# nutrino.net
KiCad netlist of a schematic drawn in EAGLE
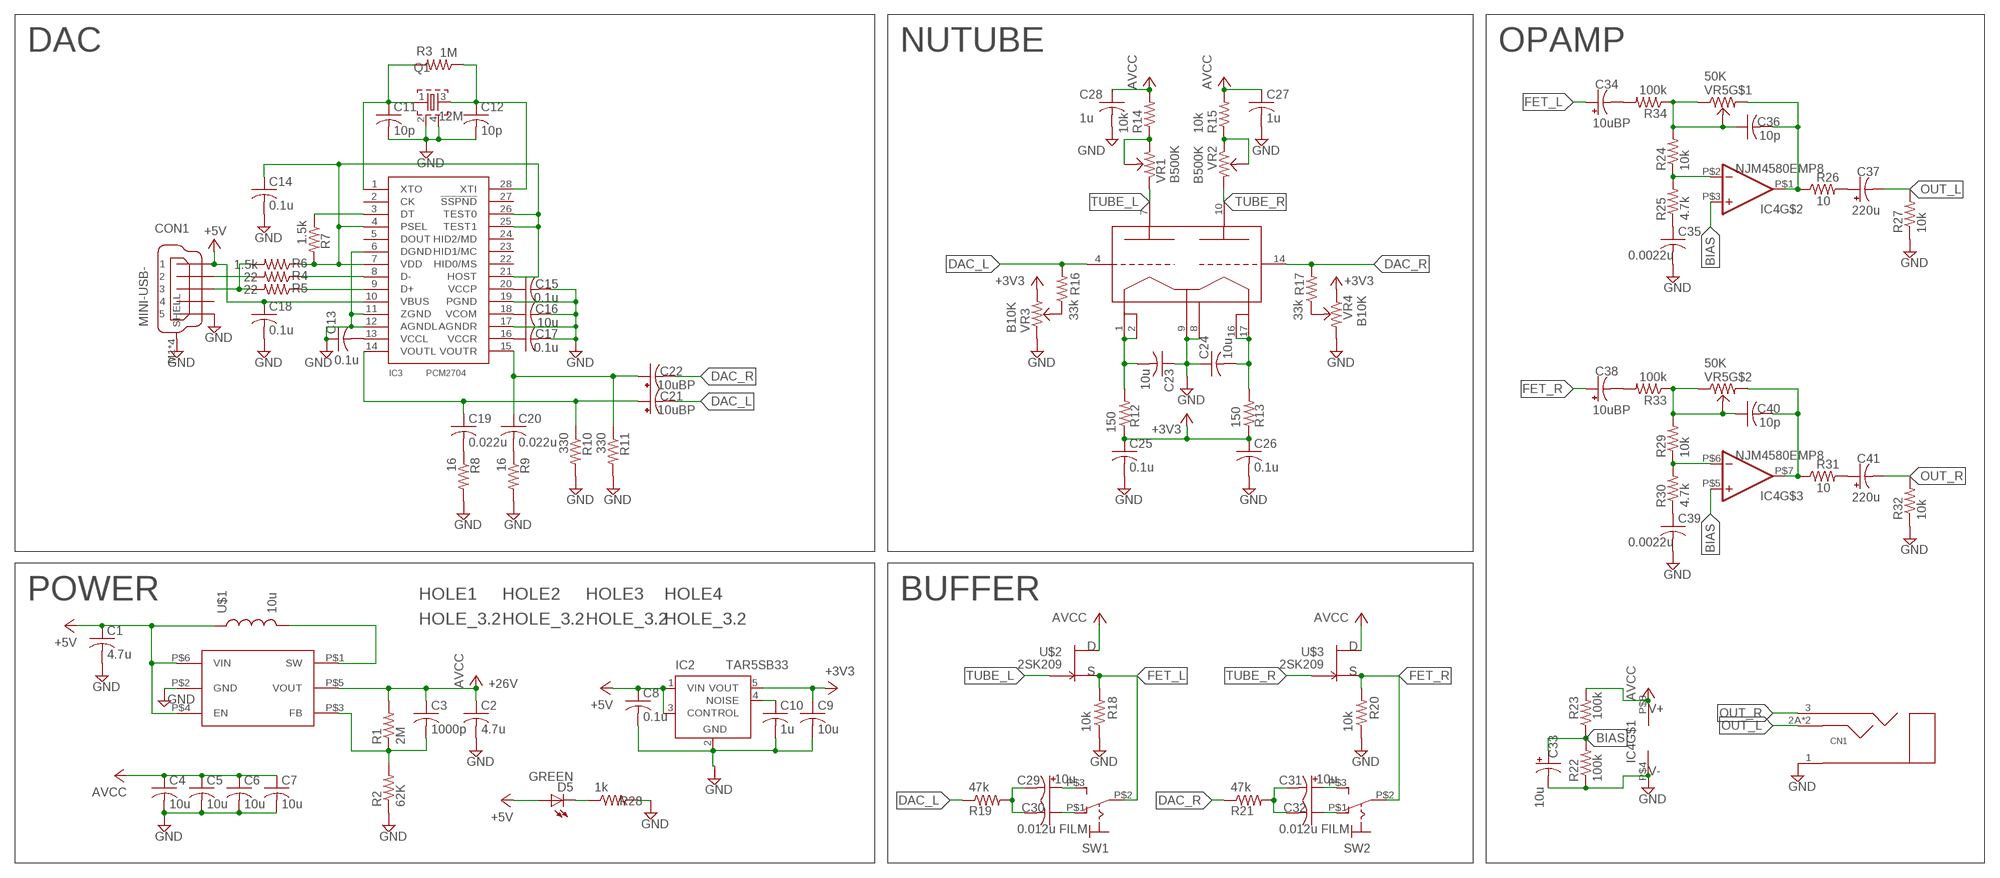
[diagram p0: schematic, sheet 1]

(export (version "E")
  (design (tool "Eeschema 10.0.6"))
  (components
    (comp (ref "C1")
      (value "4.7u")
      (footprint "eagle-import:2012-C")
      (libsource (lib "eagle-import") (part "C-2012"))
    )
    (comp (ref "C2")
      (value "4.7u")
      (footprint "eagle-import:2012-C")
      (libsource (lib "eagle-import") (part "C-2012"))
    )
    (comp (ref "C3")
      (value "1000p")
      (footprint "eagle-import:2012-C")
      (libsource (lib "eagle-import") (part "C-2012"))
    )
    (comp (ref "C4")
      (value "10u")
      (footprint "eagle-import:2012-C")
      (libsource (lib "eagle-import") (part "C-2012"))
    )
    (comp (ref "C5")
      (value "10u")
      (footprint "eagle-import:2012-C")
      (libsource (lib "eagle-import") (part "C-2012"))
    )
    (comp (ref "C6")
      (value "10u")
      (footprint "eagle-import:2012-C")
      (libsource (lib "eagle-import") (part "C-2012"))
    )
    (comp (ref "C7")
      (value "10u")
      (footprint "eagle-import:2012-C")
      (libsource (lib "eagle-import") (part "C-2012"))
    )
    (comp (ref "C8")
      (value "0.1u")
      (footprint "eagle-import:2012-C")
      (libsource (lib "eagle-import") (part "C-2012"))
    )
    (comp (ref "C9")
      (value "10u")
      (footprint "eagle-import:2012-C")
      (libsource (lib "eagle-import") (part "C-2012"))
    )
    (comp (ref "C10")
      (value "1u")
      (footprint "eagle-import:2012-C")
      (libsource (lib "eagle-import") (part "C-2012"))
    )
    (comp (ref "C11")
      (value "10p")
      (footprint "eagle-import:2012-C")
      (libsource (lib "eagle-import") (part "C-2012"))
    )
    (comp (ref "C12")
      (value "10p")
      (footprint "eagle-import:2012-C")
      (libsource (lib "eagle-import") (part "C-2012"))
    )
    (comp (ref "C13")
      (value "0.1u")
      (footprint "eagle-import:2012-C")
      (libsource (lib "eagle-import") (part "C-2012"))
    )
    (comp (ref "C14")
      (value "0.1u")
      (footprint "eagle-import:2012-C")
      (libsource (lib "eagle-import") (part "C-2012"))
    )
    (comp (ref "C15")
      (value "0.1u")
      (footprint "eagle-import:2012-C")
      (libsource (lib "eagle-import") (part "C-2012"))
    )
    (comp (ref "C16")
      (value "10u")
      (footprint "eagle-import:3216")
      (libsource (lib "eagle-import") (part "C-3216"))
    )
    (comp (ref "C17")
      (value "0.1u")
      (footprint "eagle-import:2012-C")
      (libsource (lib "eagle-import") (part "C-2012"))
    )
    (comp (ref "C18")
      (value "0.1u")
      (footprint "eagle-import:2012-C")
      (libsource (lib "eagle-import") (part "C-2012"))
    )
    (comp (ref "C19")
      (value "0.022u")
      (footprint "eagle-import:2012-C")
      (libsource (lib "eagle-import") (part "C-2012"))
    )
    (comp (ref "C20")
      (value "0.022u")
      (footprint "eagle-import:2012-C")
      (libsource (lib "eagle-import") (part "C-2012"))
    )
    (comp (ref "C21")
      (value "10uBP")
      (footprint "eagle-import:E2,5-7")
      (libsource (lib "eagle-import") (part "CC-2.5-7"))
    )
    (comp (ref "C22")
      (value "10uBP")
      (footprint "eagle-import:E2,5-7")
      (libsource (lib "eagle-import") (part "CC-2.5-7"))
    )
    (comp (ref "C23")
      (value "10u")
      (footprint "eagle-import:3216")
      (libsource (lib "eagle-import") (part "C-3216"))
    )
    (comp (ref "C24")
      (value "10u")
      (footprint "eagle-import:3216")
      (libsource (lib "eagle-import") (part "C-3216"))
    )
    (comp (ref "C25")
      (value "0.1u")
      (footprint "eagle-import:2012-C")
      (libsource (lib "eagle-import") (part "C-2012"))
    )
    (comp (ref "C26")
      (value "0.1u")
      (footprint "eagle-import:2012-C")
      (libsource (lib "eagle-import") (part "C-2012"))
    )
    (comp (ref "C27")
      (value "1u")
      (footprint "eagle-import:2012-C")
      (libsource (lib "eagle-import") (part "C-2012"))
    )
    (comp (ref "C28")
      (value "1u")
      (footprint "eagle-import:2012-C")
      (libsource (lib "eagle-import") (part "C-2012"))
    )
    (comp (ref "C29")
      (value "10u")
      (footprint "eagle-import:E2,5-7")
      (libsource (lib "eagle-import") (part "CC-2.5-7"))
    )
    (comp (ref "C30")
      (value "0.012u FILM")
      (footprint "eagle-import:C050-024X044")
      (libsource (lib "eagle-import") (part "C/5"))
    )
    (comp (ref "C31")
      (value "10u")
      (footprint "eagle-import:E2,5-7")
      (libsource (lib "eagle-import") (part "CC-2.5-7"))
    )
    (comp (ref "C32")
      (value "0.012u FILM")
      (footprint "eagle-import:C050-024X044")
      (libsource (lib "eagle-import") (part "C/5"))
    )
    (comp (ref "C33")
      (value "10u")
      (footprint "eagle-import:E2,5-7")
      (libsource (lib "eagle-import") (part "CC-2.5-7"))
    )
    (comp (ref "C34")
      (value "10uBP")
      (footprint "eagle-import:E2,5-7")
      (libsource (lib "eagle-import") (part "CC-2.5-7"))
    )
    (comp (ref "C35")
      (value "0.0022u")
      (footprint "eagle-import:2012-C")
      (libsource (lib "eagle-import") (part "C-2012"))
    )
    (comp (ref "C36")
      (value "10p")
      (footprint "eagle-import:2012-C")
      (libsource (lib "eagle-import") (part "C-2012"))
    )
    (comp (ref "C37")
      (value "220u")
      (footprint "eagle-import:E2,5-7")
      (libsource (lib "eagle-import") (part "CC-2.5-7"))
    )
    (comp (ref "C38")
      (value "10uBP")
      (footprint "eagle-import:E2,5-7")
      (libsource (lib "eagle-import") (part "CC-2.5-7"))
    )
    (comp (ref "C39")
      (value "0.0022u")
      (footprint "eagle-import:2012-C")
      (libsource (lib "eagle-import") (part "C-2012"))
    )
    (comp (ref "C40")
      (value "10p")
      (footprint "eagle-import:2012-C")
      (libsource (lib "eagle-import") (part "C-2012"))
    )
    (comp (ref "C41")
      (value "220u")
      (footprint "eagle-import:E2,5-7")
      (libsource (lib "eagle-import") (part "CC-2.5-7"))
    )
    (comp (ref "CN1")
      (value "STEREO-3.5-MJ8435")
      (footprint "eagle-import:MJ8435")
      (libsource (lib "eagle-import") (part "STEREO-3.5-MJ8435"))
    )
    (comp (ref "CON1")
      (value "MINI-USB-")
      (footprint "eagle-import:UX60A-MB-5ST")
      (libsource (lib "eagle-import") (part "MINI-USB-"))
    )
    (comp (ref "D5")
      (value "GREEN")
      (footprint "eagle-import:D2012")
      (libsource (lib "eagle-import") (part "LED-SMD2012"))
    )
    (comp (ref "HOLE1")
      (value "HOLE_3.2")
      (footprint "eagle-import:HOLE_3.2")
      (libsource (lib "eagle-import") (part "HOLE_3.2"))
    )
    (comp (ref "HOLE2")
      (value "HOLE_3.2")
      (footprint "eagle-import:HOLE_3.2")
      (libsource (lib "eagle-import") (part "HOLE_3.2"))
    )
    (comp (ref "HOLE3")
      (value "HOLE_3.2")
      (footprint "eagle-import:HOLE_3.2")
      (libsource (lib "eagle-import") (part "HOLE_3.2"))
    )
    (comp (ref "HOLE4")
      (value "HOLE_3.2")
      (footprint "eagle-import:HOLE_3.2")
      (libsource (lib "eagle-import") (part "HOLE_3.2"))
    )
    (comp (ref "IC1")
      (value "TLV61046A")
      (footprint "eagle-import:SOT23-6")
      (libsource (lib "eagle-import") (part "TLV61046A"))
    )
    (comp (ref "IC2")
      (value "TAR5SB33")
      (footprint "eagle-import:SSOP5-P-0.95")
      (libsource (lib "eagle-import") (part "TAR5SB33"))
    )
    (comp (ref "IC3")
      (value "PCM2704")
      (footprint "eagle-import:SSOP28")
      (libsource (lib "eagle-import") (part "PCM2704"))
    )
    (comp (ref "IC4")
      (value "NJM4580EMP8")
      (footprint "eagle-import:EMP8")
      (libsource (lib "eagle-import") (part "NJM4580EMP8"))
    )
    (comp (ref "Q1")
      (value "12M")
      (footprint "eagle-import:FA-238V")
      (libsource (lib "eagle-import") (part "FA-238V"))
    )
    (comp (ref "R1")
      (value "2M")
      (footprint "eagle-import:2012-R")
      (libsource (lib "eagle-import") (part "Passive_Robotech_29513872_R-2012"))
    )
    (comp (ref "R2")
      (value "62K")
      (footprint "eagle-import:2012-R")
      (libsource (lib "eagle-import") (part "Passive_Robotech_29513872_R-2012"))
    )
    (comp (ref "R3")
      (value "1M")
      (footprint "eagle-import:2012-R")
      (libsource (lib "eagle-import") (part "Passive_Robotech_29513872_R-2012"))
    )
    (comp (ref "R4")
      (value "22")
      (footprint "eagle-import:2012-R")
      (libsource (lib "eagle-import") (part "Passive_Robotech_29513872_R-2012"))
    )
    (comp (ref "R5")
      (value "22")
      (footprint "eagle-import:2012-R")
      (libsource (lib "eagle-import") (part "Passive_Robotech_29513872_R-2012"))
    )
    (comp (ref "R6")
      (value "1.5k")
      (footprint "eagle-import:2012-R")
      (libsource (lib "eagle-import") (part "Passive_Robotech_29513872_R-2012"))
    )
    (comp (ref "R7")
      (value "1.5k")
      (footprint "eagle-import:2012-R")
      (libsource (lib "eagle-import") (part "Passive_Robotech_29513872_R-2012"))
    )
    (comp (ref "R8")
      (value "16")
      (footprint "eagle-import:2012-R")
      (libsource (lib "eagle-import") (part "Passive_Robotech_29513872_R-2012"))
    )
    (comp (ref "R9")
      (value "16")
      (footprint "eagle-import:2012-R")
      (libsource (lib "eagle-import") (part "Passive_Robotech_29513872_R-2012"))
    )
    (comp (ref "R10")
      (value "330")
      (footprint "eagle-import:2012-R")
      (libsource (lib "eagle-import") (part "Passive_Robotech_29513872_R-2012"))
    )
    (comp (ref "R11")
      (value "330")
      (footprint "eagle-import:2012-R")
      (libsource (lib "eagle-import") (part "Passive_Robotech_29513872_R-2012"))
    )
    (comp (ref "R12")
      (value "150")
      (footprint "eagle-import:2012-R")
      (libsource (lib "eagle-import") (part "R-2012"))
    )
    (comp (ref "R13")
      (value "150")
      (footprint "eagle-import:2012-R")
      (libsource (lib "eagle-import") (part "R-2012"))
    )
    (comp (ref "R14")
      (value "10k")
      (footprint "eagle-import:2012-R")
      (libsource (lib "eagle-import") (part "R-2012"))
    )
    (comp (ref "R15")
      (value "10k")
      (footprint "eagle-import:2012-R")
      (libsource (lib "eagle-import") (part "R-2012"))
    )
    (comp (ref "R16")
      (value "33k")
      (footprint "eagle-import:2012-R")
      (libsource (lib "eagle-import") (part "R-2012"))
    )
    (comp (ref "R17")
      (value "33k")
      (footprint "eagle-import:2012-R")
      (libsource (lib "eagle-import") (part "R-2012"))
    )
    (comp (ref "R18")
      (value "10k")
      (footprint "eagle-import:2012-R")
      (libsource (lib "eagle-import") (part "R-2012"))
    )
    (comp (ref "R19")
      (value "47k")
      (footprint "eagle-import:2012-R")
      (libsource (lib "eagle-import") (part "R-2012"))
    )
    (comp (ref "R20")
      (value "10k")
      (footprint "eagle-import:2012-R")
      (libsource (lib "eagle-import") (part "R-2012"))
    )
    (comp (ref "R21")
      (value "47k")
      (footprint "eagle-import:2012-R")
      (libsource (lib "eagle-import") (part "R-2012"))
    )
    (comp (ref "R22")
      (value "100k")
      (footprint "eagle-import:2012-R")
      (libsource (lib "eagle-import") (part "R-2012"))
    )
    (comp (ref "R23")
      (value "100k")
      (footprint "eagle-import:2012-R")
      (libsource (lib "eagle-import") (part "R-2012"))
    )
    (comp (ref "R24")
      (value "10k")
      (footprint "eagle-import:2012-R")
      (libsource (lib "eagle-import") (part "R-2012"))
    )
    (comp (ref "R25")
      (value "4.7k")
      (footprint "eagle-import:2012-R")
      (libsource (lib "eagle-import") (part "R-2012"))
    )
    (comp (ref "R26")
      (value "10")
      (footprint "eagle-import:4532")
      (libsource (lib "eagle-import") (part "R-4532"))
    )
    (comp (ref "R27")
      (value "10k")
      (footprint "eagle-import:2012-R")
      (libsource (lib "eagle-import") (part "R-2012"))
    )
    (comp (ref "R28")
      (value "1k")
      (footprint "eagle-import:2012-R")
      (libsource (lib "eagle-import") (part "R-2012"))
    )
    (comp (ref "R29")
      (value "10k")
      (footprint "eagle-import:2012-R")
      (libsource (lib "eagle-import") (part "R-2012"))
    )
    (comp (ref "R30")
      (value "4.7k")
      (footprint "eagle-import:2012-R")
      (libsource (lib "eagle-import") (part "R-2012"))
    )
    (comp (ref "R31")
      (value "10")
      (footprint "eagle-import:4532")
      (libsource (lib "eagle-import") (part "R-4532"))
    )
    (comp (ref "R32")
      (value "10k")
      (footprint "eagle-import:2012-R")
      (libsource (lib "eagle-import") (part "R-2012"))
    )
    (comp (ref "R33")
      (value "100k")
      (footprint "eagle-import:2012-R")
      (libsource (lib "eagle-import") (part "R-2012"))
    )
    (comp (ref "R34")
      (value "100k")
      (footprint "eagle-import:2012-R")
      (libsource (lib "eagle-import") (part "R-2012"))
    )
    (comp (ref "SW1")
      (value "SLIDESW_SS12D01G4")
      (footprint "eagle-import:SS12D01G4")
      (libsource (lib "eagle-import") (part "SLIDESW_SS12D01G4"))
    )
    (comp (ref "SW2")
      (value "SLIDESW_SS12D01G4")
      (footprint "eagle-import:SS12D01G4")
      (libsource (lib "eagle-import") (part "SLIDESW_SS12D01G4"))
    )
    (comp (ref "U$1")
      (value "10u")
      (footprint "eagle-import:NR10050T")
      (libsource (lib "eagle-import") (part "INDUCTOR-NR10050T"))
    )
    (comp (ref "U$2")
      (value "2SK209")
      (footprint "eagle-import:SC59")
      (libsource (lib "eagle-import") (part "2SK209"))
    )
    (comp (ref "U$3")
      (value "2SK209")
      (footprint "eagle-import:SC59")
      (libsource (lib "eagle-import") (part "2SK209"))
    )
    (comp (ref "U1")
      (value "NUTUBE_6P1_1")
      (footprint "eagle-import:NUTUBE_6P1_1")
      (libsource (lib "eagle-import") (part "NUTUBE_6P1_1"))
    )
    (comp (ref "VR1")
      (value "B500K")
      (footprint "eagle-import:VR2")
      (libsource (lib "eagle-import") (part "VR2"))
    )
    (comp (ref "VR2")
      (value "B500K")
      (footprint "eagle-import:VR2")
      (libsource (lib "eagle-import") (part "VR2"))
    )
    (comp (ref "VR3")
      (value "B10K")
      (footprint "eagle-import:VR2")
      (libsource (lib "eagle-import") (part "VR2"))
    )
    (comp (ref "VR4")
      (value "B10K")
      (footprint "eagle-import:VR2")
      (libsource (lib "eagle-import") (part "VR2"))
    )
    (comp (ref "VR5")
      (value "50K")
      (footprint "eagle-import:VR2C")
      (libsource (lib "eagle-import") (part "VR2C"))
    )
  )
  (nets
    (net (code "1") (name "+3V3") (class "Default")
      (node (ref "C25") (pin "1") (pinfunction "1_1") (pintype "passive"))
      (node (ref "C26") (pin "1") (pinfunction "1_1") (pintype "passive"))
      (node (ref "C9") (pin "1") (pinfunction "1_1") (pintype "passive"))
      (node (ref "IC2") (pin "5") (pinfunction "VOUT_5") (pintype "power_in"))
      (node (ref "R12") (pin "1") (pinfunction "1_1") (pintype "passive"))
      (node (ref "R13") (pin "1") (pinfunction "1_1") (pintype "passive"))
      (node (ref "VR3") (pin "2") (pinfunction "2_2") (pintype "passive"))
      (node (ref "VR4") (pin "1") (pinfunction "1_1") (pintype "passive"))
    )
    (net (code "2") (name "+5V") (class "Default")
      (node (ref "C1") (pin "1") (pinfunction "1_1") (pintype "passive"))
      (node (ref "C18") (pin "1") (pinfunction "1_1") (pintype "passive"))
      (node (ref "C8") (pin "1") (pinfunction "1_1") (pintype "passive"))
      (node (ref "CON1") (pin "1") (pinfunction "1_1") (pintype "input"))
      (node (ref "D5") (pin "A") (pinfunction "A_A") (pintype "passive"))
      (node (ref "IC1") (pin "P$4") (pinfunction "EN_P$4") (pintype "bidirectional"))
      (node (ref "IC1") (pin "P$6") (pinfunction "VIN_P$6") (pintype "bidirectional"))
      (node (ref "IC2") (pin "1") (pinfunction "VIN_1") (pintype "input"))
      (node (ref "IC2") (pin "3") (pinfunction "CONTROL_3") (pintype "input"))
      (node (ref "IC3") (pin "10") (pinfunction "VBUS_10") (pintype "power_in"))
      (node (ref "U$1") (pin "1") (pinfunction "1_1") (pintype "passive"))
    )
    (net (code "3") (name "AVCC") (class "Default")
      (node (ref "C2") (pin "1") (pinfunction "1_1") (pintype "passive"))
      (node (ref "C27") (pin "1") (pinfunction "1_1") (pintype "passive"))
      (node (ref "C28") (pin "1") (pinfunction "1_1") (pintype "passive"))
      (node (ref "C3") (pin "1") (pinfunction "1_1") (pintype "passive"))
      (node (ref "C4") (pin "1") (pinfunction "1_1") (pintype "passive"))
      (node (ref "C5") (pin "1") (pinfunction "1_1") (pintype "passive"))
      (node (ref "C6") (pin "1") (pinfunction "1_1") (pintype "passive"))
      (node (ref "C7") (pin "1") (pinfunction "1_1") (pintype "passive"))
      (node (ref "IC1") (pin "P$5") (pinfunction "VOUT_P$5") (pintype "bidirectional"))
      (node (ref "IC4") (pin "P$8") (pinfunction "V+_P$8") (pintype "power_in"))
      (node (ref "R1") (pin "2") (pinfunction "2_2") (pintype "passive"))
      (node (ref "R14") (pin "2") (pinfunction "2_2") (pintype "passive"))
      (node (ref "R15") (pin "2") (pinfunction "2_2") (pintype "passive"))
      (node (ref "R23") (pin "2") (pinfunction "2_2") (pintype "passive"))
      (node (ref "U$2") (pin "E") (pinfunction "D_E") (pintype "passive"))
      (node (ref "U$3") (pin "E") (pinfunction "D_E") (pintype "passive"))
    )
    (net (code "4") (name "BIAS") (class "Default")
      (node (ref "C33") (pin "+") (pinfunction "+_+") (pintype "passive"))
      (node (ref "IC4") (pin "P$3") (pinfunction "+IN_P$3") (pintype "input"))
      (node (ref "IC4") (pin "P$5") (pinfunction "+IN_P$5") (pintype "input"))
      (node (ref "R22") (pin "2") (pinfunction "2_2") (pintype "passive"))
      (node (ref "R23") (pin "1") (pinfunction "1_1") (pintype "passive"))
    )
    (net (code "5") (name "DAC_L") (class "Default")
      (node (ref "C21") (pin "-") (pinfunction "-_-") (pintype "passive"))
      (node (ref "R16") (pin "2") (pinfunction "2_2") (pintype "passive"))
      (node (ref "R19") (pin "1") (pinfunction "1_1") (pintype "passive"))
      (node (ref "U1") (pin "4") (pinfunction "G1_4_4") (pintype "passive"))
    )
    (net (code "6") (name "DAC_R") (class "Default")
      (node (ref "C22") (pin "-") (pinfunction "-_-") (pintype "passive"))
      (node (ref "R17") (pin "2") (pinfunction "2_2") (pintype "passive"))
      (node (ref "R21") (pin "1") (pinfunction "1_1") (pintype "passive"))
      (node (ref "U1") (pin "14") (pinfunction "G2_14_14") (pintype "passive"))
    )
    (net (code "7") (name "FET_L") (class "Default")
      (node (ref "C34") (pin "+") (pinfunction "+_+") (pintype "passive"))
      (node (ref "R18") (pin "2") (pinfunction "2_2") (pintype "passive"))
      (node (ref "SW1") (pin "P$2") (pinfunction "P_P$2") (pintype "passive"))
      (node (ref "U$2") (pin "B") (pinfunction "S_B") (pintype "passive"))
    )
    (net (code "8") (name "FET_R") (class "Default")
      (node (ref "C38") (pin "+") (pinfunction "+_+") (pintype "passive"))
      (node (ref "R20") (pin "2") (pinfunction "2_2") (pintype "passive"))
      (node (ref "SW2") (pin "P$2") (pinfunction "P_P$2") (pintype "passive"))
      (node (ref "U$3") (pin "B") (pinfunction "S_B") (pintype "passive"))
    )
    (net (code "9") (name "GND") (class "Default")
      (node (ref "C1") (pin "2") (pinfunction "2_2") (pintype "passive"))
      (node (ref "C10") (pin "2") (pinfunction "2_2") (pintype "passive"))
      (node (ref "C11") (pin "2") (pinfunction "2_2") (pintype "passive"))
      (node (ref "C12") (pin "2") (pinfunction "2_2") (pintype "passive"))
      (node (ref "C13") (pin "1") (pinfunction "1_1") (pintype "passive"))
      (node (ref "C14") (pin "2") (pinfunction "2_2") (pintype "passive"))
      (node (ref "C15") (pin "2") (pinfunction "2_2") (pintype "passive"))
      (node (ref "C16") (pin "2") (pinfunction "2_2") (pintype "passive"))
      (node (ref "C17") (pin "2") (pinfunction "2_2") (pintype "passive"))
      (node (ref "C18") (pin "2") (pinfunction "2_2") (pintype "passive"))
      (node (ref "C2") (pin "2") (pinfunction "2_2") (pintype "passive"))
      (node (ref "C23") (pin "1") (pinfunction "1_1") (pintype "passive"))
      (node (ref "C24") (pin "1") (pinfunction "1_1") (pintype "passive"))
      (node (ref "C25") (pin "2") (pinfunction "2_2") (pintype "passive"))
      (node (ref "C26") (pin "2") (pinfunction "2_2") (pintype "passive"))
      (node (ref "C27") (pin "2") (pinfunction "2_2") (pintype "passive"))
      (node (ref "C28") (pin "2") (pinfunction "2_2") (pintype "passive"))
      (node (ref "C33") (pin "-") (pinfunction "-_-") (pintype "passive"))
      (node (ref "C35") (pin "2") (pinfunction "2_2") (pintype "passive"))
      (node (ref "C39") (pin "2") (pinfunction "2_2") (pintype "passive"))
      (node (ref "C4") (pin "2") (pinfunction "2_2") (pintype "passive"))
      (node (ref "C5") (pin "2") (pinfunction "2_2") (pintype "passive"))
      (node (ref "C6") (pin "2") (pinfunction "2_2") (pintype "passive"))
      (node (ref "C7") (pin "2") (pinfunction "2_2") (pintype "passive"))
      (node (ref "C8") (pin "2") (pinfunction "2_2") (pintype "passive"))
      (node (ref "C9") (pin "2") (pinfunction "2_2") (pintype "passive"))
      (node (ref "CN1") (pin "1") (pinfunction "SLEEVE_1") (pintype "passive"))
      (node (ref "CON1") (pin "5") (pinfunction "5_5") (pintype "input"))
      (node (ref "CON1") (pin "M1") (pinfunction "SHELL_M1") (pintype "bidirectional"))
      (node (ref "CON1") (pin "M2") (pinfunction "SHELL_M2") (pintype "bidirectional"))
      (node (ref "CON1") (pin "M3") (pinfunction "SHELL_M3") (pintype "bidirectional"))
      (node (ref "CON1") (pin "M4") (pinfunction "SHELL_M4") (pintype "bidirectional"))
      (node (ref "IC1") (pin "P$2") (pinfunction "GND_P$2") (pintype "bidirectional"))
      (node (ref "IC2") (pin "2") (pinfunction "GND_2") (pintype "power_in"))
      (node (ref "IC3") (pin "11") (pinfunction "ZGND_11") (pintype "power_in"))
      (node (ref "IC3") (pin "12") (pinfunction "AGNDL_12") (pintype "power_in"))
      (node (ref "IC3") (pin "17") (pinfunction "AGNDR_17") (pintype "power_in"))
      (node (ref "IC3") (pin "19") (pinfunction "PGND_19") (pintype "power_in"))
      (node (ref "IC3") (pin "6") (pinfunction "DGND_6") (pintype "power_in"))
      (node (ref "IC4") (pin "P$4") (pinfunction "V-_P$4") (pintype "power_in"))
      (node (ref "Q1") (pin "2") (pinfunction "2_2") (pintype "passive"))
      (node (ref "Q1") (pin "4") (pinfunction "4_4") (pintype "passive"))
      (node (ref "R10") (pin "2") (pinfunction "2_2") (pintype "passive"))
      (node (ref "R11") (pin "2") (pinfunction "2_2") (pintype "passive"))
      (node (ref "R18") (pin "1") (pinfunction "1_1") (pintype "passive"))
      (node (ref "R2") (pin "1") (pinfunction "1_1") (pintype "passive"))
      (node (ref "R20") (pin "1") (pinfunction "1_1") (pintype "passive"))
      (node (ref "R22") (pin "1") (pinfunction "1_1") (pintype "passive"))
      (node (ref "R27") (pin "1") (pinfunction "1_1") (pintype "passive"))
      (node (ref "R28") (pin "2") (pinfunction "2_2") (pintype "passive"))
      (node (ref "R32") (pin "1") (pinfunction "1_1") (pintype "passive"))
      (node (ref "R8") (pin "2") (pinfunction "2_2") (pintype "passive"))
      (node (ref "R9") (pin "2") (pinfunction "2_2") (pintype "passive"))
      (node (ref "U1") (pin "8") (pinfunction "GND_8_8") (pintype "power_in"))
      (node (ref "U1") (pin "9") (pinfunction "F2_9_9") (pintype "passive"))
      (node (ref "VR3") (pin "1") (pinfunction "1_1") (pintype "passive"))
      (node (ref "VR4") (pin "2") (pinfunction "2_2") (pintype "passive"))
    )
    (net (code "10") (name "Net-(C19-Pad2)") (class "Default")
      (node (ref "C19") (pin "2") (pinfunction "2_2") (pintype "passive"))
      (node (ref "R8") (pin "1") (pinfunction "1_1") (pintype "passive"))
    )
    (net (code "11") (name "Net-(C20-Pad2)") (class "Default")
      (node (ref "C20") (pin "2") (pinfunction "2_2") (pintype "passive"))
      (node (ref "R9") (pin "1") (pinfunction "1_1") (pintype "passive"))
    )
    (net (code "12") (name "Net-(C29-Pad-)") (class "Default")
      (node (ref "C29") (pin "-") (pinfunction "-_-") (pintype "passive"))
      (node (ref "C30") (pin "2") (pinfunction "2_2") (pintype "passive"))
      (node (ref "R19") (pin "2") (pinfunction "2_2") (pintype "passive"))
    )
    (net (code "13") (name "Net-(C31-Pad-)") (class "Default")
      (node (ref "C31") (pin "-") (pinfunction "-_-") (pintype "passive"))
      (node (ref "C32") (pin "2") (pinfunction "2_2") (pintype "passive"))
      (node (ref "R21") (pin "2") (pinfunction "2_2") (pintype "passive"))
    )
    (net (code "14") (name "Net-(C34-Pad-)") (class "Default")
      (node (ref "C34") (pin "-") (pinfunction "-_-") (pintype "passive"))
      (node (ref "R34") (pin "2") (pinfunction "2_2") (pintype "passive"))
    )
    (net (code "15") (name "Net-(C35-Pad1)") (class "Default")
      (node (ref "C35") (pin "1") (pinfunction "1_1") (pintype "passive"))
      (node (ref "R25") (pin "1") (pinfunction "1_1") (pintype "passive"))
    )
    (net (code "16") (name "Net-(C37-Pad+)") (class "Default")
      (node (ref "C37") (pin "+") (pinfunction "+_+") (pintype "passive"))
      (node (ref "R26") (pin "2") (pinfunction "2_2") (pintype "passive"))
    )
    (net (code "17") (name "Net-(C38-Pad-)") (class "Default")
      (node (ref "C38") (pin "-") (pinfunction "-_-") (pintype "passive"))
      (node (ref "R33") (pin "2") (pinfunction "2_2") (pintype "passive"))
    )
    (net (code "18") (name "Net-(C39-Pad1)") (class "Default")
      (node (ref "C39") (pin "1") (pinfunction "1_1") (pintype "passive"))
      (node (ref "R30") (pin "1") (pinfunction "1_1") (pintype "passive"))
    )
    (net (code "19") (name "Net-(C41-Pad+)") (class "Default")
      (node (ref "C41") (pin "+") (pinfunction "+_+") (pintype "passive"))
      (node (ref "R31") (pin "2") (pinfunction "2_2") (pintype "passive"))
    )
    (net (code "20") (name "Net-(CON1-Pad2)") (class "Default")
      (node (ref "CON1") (pin "2") (pinfunction "2_2") (pintype "input"))
      (node (ref "R4") (pin "2") (pinfunction "2_2") (pintype "passive"))
    )
    (net (code "21") (name "Net-(CON1-Pad3)") (class "Default")
      (node (ref "CON1") (pin "3") (pinfunction "3_3") (pintype "input"))
      (node (ref "R5") (pin "2") (pinfunction "2_2") (pintype "passive"))
      (node (ref "R6") (pin "2") (pinfunction "2_2") (pintype "passive"))
    )
    (net (code "22") (name "Net-(D5-PadK)") (class "Default")
      (node (ref "D5") (pin "K") (pinfunction "K_K") (pintype "passive"))
      (node (ref "R28") (pin "1") (pinfunction "1_1") (pintype "passive"))
    )
    (net (code "23") (name "Net-(IC1-FB)") (class "Default")
      (node (ref "C3") (pin "2") (pinfunction "2_2") (pintype "passive"))
      (node (ref "IC1") (pin "P$3") (pinfunction "FB_P$3") (pintype "bidirectional"))
      (node (ref "R1") (pin "1") (pinfunction "1_1") (pintype "passive"))
      (node (ref "R2") (pin "2") (pinfunction "2_2") (pintype "passive"))
    )
    (net (code "24") (name "Net-(IC1-SW)") (class "Default")
      (node (ref "IC1") (pin "P$1") (pinfunction "SW_P$1") (pintype "bidirectional"))
      (node (ref "U$1") (pin "2") (pinfunction "2_2") (pintype "passive"))
    )
    (net (code "25") (name "Net-(IC2-NOISE)") (class "Default")
      (node (ref "C10") (pin "1") (pinfunction "1_1") (pintype "passive"))
      (node (ref "IC2") (pin "4") (pinfunction "NOISE_4") (pintype "passive"))
    )
    (net (code "26") (name "Net-(IC3-D+)") (class "Default")
      (node (ref "IC3") (pin "9") (pinfunction "D+_9") (pintype "bidirectional"))
      (node (ref "R5") (pin "1") (pinfunction "1_1") (pintype "passive"))
    )
    (net (code "27") (name "Net-(IC3-D-)") (class "Default")
      (node (ref "IC3") (pin "8") (pinfunction "D-_8") (pintype "bidirectional"))
      (node (ref "R4") (pin "1") (pinfunction "1_1") (pintype "passive"))
    )
    (net (code "28") (name "Net-(IC3-DT)") (class "Default")
      (node (ref "IC3") (pin "3") (pinfunction "DT_3") (pintype "bidirectional"))
      (node (ref "R7") (pin "1") (pinfunction "1_1") (pintype "passive"))
    )
    (net (code "29") (name "Net-(IC3-HOST)") (class "Default")
      (node (ref "C14") (pin "1") (pinfunction "1_1") (pintype "passive"))
      (node (ref "IC3") (pin "21") (pinfunction "HOST_21") (pintype "input"))
      (node (ref "IC3") (pin "25") (pinfunction "TEST1_25") (pintype "input"))
      (node (ref "IC3") (pin "26") (pinfunction "TEST0_26") (pintype "input"))
      (node (ref "IC3") (pin "4") (pinfunction "PSEL_4") (pintype "input"))
      (node (ref "IC3") (pin "7") (pinfunction "VDD_7") (pintype "power_in"))
      (node (ref "R6") (pin "1") (pinfunction "1_1") (pintype "passive"))
      (node (ref "R7") (pin "2") (pinfunction "2_2") (pintype "passive"))
    )
    (net (code "30") (name "Net-(IC3-VCCL)") (class "Default")
      (node (ref "C13") (pin "2") (pinfunction "2_2") (pintype "passive"))
      (node (ref "IC3") (pin "13") (pinfunction "VCCL_13") (pintype "power_in"))
    )
    (net (code "31") (name "Net-(IC3-VCCP)") (class "Default")
      (node (ref "C15") (pin "1") (pinfunction "1_1") (pintype "passive"))
      (node (ref "IC3") (pin "20") (pinfunction "VCCP_20") (pintype "power_in"))
    )
    (net (code "32") (name "Net-(IC3-VCCR)") (class "Default")
      (node (ref "C17") (pin "1") (pinfunction "1_1") (pintype "passive"))
      (node (ref "IC3") (pin "16") (pinfunction "VCCR_16") (pintype "power_in"))
    )
    (net (code "33") (name "Net-(IC3-VCOM)") (class "Default")
      (node (ref "C16") (pin "1") (pinfunction "1_1") (pintype "passive"))
      (node (ref "IC3") (pin "18") (pinfunction "VCOM_18") (pintype "output"))
    )
    (net (code "34") (name "Net-(IC3-VOUTL)") (class "Default")
      (node (ref "C19") (pin "1") (pinfunction "1_1") (pintype "passive"))
      (node (ref "C21") (pin "+") (pinfunction "+_+") (pintype "passive"))
      (node (ref "IC3") (pin "14") (pinfunction "VOUTL_14") (pintype "output"))
      (node (ref "R10") (pin "1") (pinfunction "1_1") (pintype "passive"))
    )
    (net (code "35") (name "Net-(IC3-VOUTR)") (class "Default")
      (node (ref "C20") (pin "1") (pinfunction "1_1") (pintype "passive"))
      (node (ref "C22") (pin "+") (pinfunction "+_+") (pintype "passive"))
      (node (ref "IC3") (pin "15") (pinfunction "VOUTR_15") (pintype "output"))
      (node (ref "R11") (pin "1") (pinfunction "1_1") (pintype "passive"))
    )
    (net (code "36") (name "Net-(IC3-XTI)") (class "Default")
      (node (ref "C12") (pin "1") (pinfunction "1_1") (pintype "passive"))
      (node (ref "IC3") (pin "28") (pinfunction "XTI_28") (pintype "input"))
      (node (ref "Q1") (pin "3") (pinfunction "3_3") (pintype "passive"))
      (node (ref "R3") (pin "1") (pinfunction "1_1") (pintype "passive"))
    )
    (net (code "37") (name "Net-(IC3-XTO)") (class "Default")
      (node (ref "C11") (pin "1") (pinfunction "1_1") (pintype "passive"))
      (node (ref "IC3") (pin "1") (pinfunction "XTO_1") (pintype "output"))
      (node (ref "Q1") (pin "1") (pinfunction "1_1") (pintype "passive"))
      (node (ref "R3") (pin "2") (pinfunction "2_2") (pintype "passive"))
    )
    (net (code "38") (name "Net-(IC4B--IN)") (class "Default")
      (node (ref "IC4") (pin "P$2") (pinfunction "-IN_P$2") (pintype "input"))
      (node (ref "R24") (pin "1") (pinfunction "1_1") (pintype "passive"))
      (node (ref "R25") (pin "2") (pinfunction "2_2") (pintype "passive"))
    )
    (net (code "39") (name "Net-(IC4B-OUT)") (class "Default")
      (node (ref "C36") (pin "2") (pinfunction "2_2") (pintype "passive"))
      (node (ref "IC4") (pin "P$1") (pinfunction "OUT_P$1") (pintype "output"))
      (node (ref "R26") (pin "1") (pinfunction "1_1") (pintype "passive"))
      (node (ref "VR5") (pin "1") (pinfunction "2_1") (pintype "passive"))
    )
    (net (code "40") (name "Net-(IC4C--IN)") (class "Default")
      (node (ref "IC4") (pin "P$6") (pinfunction "-IN_P$6") (pintype "input"))
      (node (ref "R29") (pin "1") (pinfunction "1_1") (pintype "passive"))
      (node (ref "R30") (pin "2") (pinfunction "2_2") (pintype "passive"))
    )
    (net (code "41") (name "Net-(IC4C-OUT)") (class "Default")
      (node (ref "C40") (pin "2") (pinfunction "2_2") (pintype "passive"))
      (node (ref "IC4") (pin "P$7") (pinfunction "OUT_P$7") (pintype "output"))
      (node (ref "R31") (pin "1") (pinfunction "1_1") (pintype "passive"))
      (node (ref "VR5") (pin "1'") (pinfunction "2_1'") (pintype "passive"))
    )
    (net (code "42") (name "Net-(R14-Pad1)") (class "Default")
      (node (ref "R14") (pin "1") (pinfunction "1_1") (pintype "passive"))
      (node (ref "VR1") (pin "2") (pinfunction "2_2") (pintype "passive"))
      (node (ref "VR1") (pin "BR") (pinfunction "BR_BR") (pintype "passive"))
    )
    (net (code "43") (name "Net-(R15-Pad1)") (class "Default")
      (node (ref "R15") (pin "1") (pinfunction "1_1") (pintype "passive"))
      (node (ref "VR2") (pin "1") (pinfunction "1_1") (pintype "passive"))
      (node (ref "VR2") (pin "BR") (pinfunction "BR_BR") (pintype "passive"))
    )
    (net (code "44") (name "Net-(R16-Pad1)") (class "Default")
      (node (ref "R16") (pin "1") (pinfunction "1_1") (pintype "passive"))
      (node (ref "VR3") (pin "BR") (pinfunction "BR_BR") (pintype "passive"))
    )
    (net (code "45") (name "Net-(R17-Pad1)") (class "Default")
      (node (ref "R17") (pin "1") (pinfunction "1_1") (pintype "passive"))
      (node (ref "VR4") (pin "BR") (pinfunction "BR_BR") (pintype "passive"))
    )
    (net (code "46") (name "Net-(SW1-O)") (class "Default")
      (node (ref "C30") (pin "1") (pinfunction "1_1") (pintype "passive"))
      (node (ref "SW1") (pin "P$1") (pinfunction "O_P$1") (pintype "passive"))
    )
    (net (code "47") (name "Net-(SW1-S)") (class "Default")
      (node (ref "C29") (pin "+") (pinfunction "+_+") (pintype "passive"))
      (node (ref "SW1") (pin "P$3") (pinfunction "S_P$3") (pintype "passive"))
    )
    (net (code "48") (name "Net-(SW2-O)") (class "Default")
      (node (ref "C32") (pin "1") (pinfunction "1_1") (pintype "passive"))
      (node (ref "SW2") (pin "P$1") (pinfunction "O_P$1") (pintype "passive"))
    )
    (net (code "49") (name "Net-(SW2-S)") (class "Default")
      (node (ref "C31") (pin "+") (pinfunction "+_+") (pintype "passive"))
      (node (ref "SW2") (pin "P$3") (pinfunction "S_P$3") (pintype "passive"))
    )
    (net (code "50") (name "Net-(U1-F1_1)") (class "Default")
      (node (ref "C23") (pin "2") (pinfunction "2_2") (pintype "passive"))
      (node (ref "R12") (pin "2") (pinfunction "2_2") (pintype "passive"))
      (node (ref "U1") (pin "1") (pinfunction "F1_1_1") (pintype "passive"))
      (node (ref "U1") (pin "2") (pinfunction "F1_2_2") (pintype "passive"))
    )
    (net (code "51") (name "Net-(U1-F3_16)") (class "Default")
      (node (ref "C24") (pin "2") (pinfunction "2_2") (pintype "passive"))
      (node (ref "R13") (pin "2") (pinfunction "2_2") (pintype "passive"))
      (node (ref "U1") (pin "16") (pinfunction "F3_16_16") (pintype "passive"))
      (node (ref "U1") (pin "17") (pinfunction "F3_17_17") (pintype "passive"))
    )
    (net (code "52") (name "Net-(VR5A-1)") (class "Default")
      (node (ref "C36") (pin "1") (pinfunction "1_1") (pintype "passive"))
      (node (ref "R24") (pin "2") (pinfunction "2_2") (pintype "passive"))
      (node (ref "R34") (pin "1") (pinfunction "1_1") (pintype "passive"))
      (node (ref "VR5") (pin "2") (pinfunction "BR_2") (pintype "passive"))
      (node (ref "VR5") (pin "3") (pinfunction "1_3") (pintype "passive"))
    )
    (net (code "53") (name "Net-(VR5B-1)") (class "Default")
      (node (ref "C40") (pin "1") (pinfunction "1_1") (pintype "passive"))
      (node (ref "R29") (pin "2") (pinfunction "2_2") (pintype "passive"))
      (node (ref "R33") (pin "1") (pinfunction "1_1") (pintype "passive"))
      (node (ref "VR5") (pin "2'") (pinfunction "BR_2'") (pintype "passive"))
      (node (ref "VR5") (pin "3'") (pinfunction "1_3'") (pintype "passive"))
    )
    (net (code "54") (name "OUT_L") (class "Default")
      (node (ref "C37") (pin "-") (pinfunction "-_-") (pintype "passive"))
      (node (ref "CN1") (pin "2A") (pinfunction "RING_2A") (pintype "passive"))
      (node (ref "CN1") (pin "2B") (pinfunction "RING_2B") (pintype "passive"))
      (node (ref "R27") (pin "2") (pinfunction "2_2") (pintype "passive"))
    )
    (net (code "55") (name "OUT_R") (class "Default")
      (node (ref "C41") (pin "-") (pinfunction "-_-") (pintype "passive"))
      (node (ref "CN1") (pin "3") (pinfunction "TIP_3") (pintype "passive"))
      (node (ref "R32") (pin "2") (pinfunction "2_2") (pintype "passive"))
    )
    (net (code "56") (name "TUBE_L") (class "Default")
      (node (ref "U$2") (pin "C") (pinfunction "G_C") (pintype "passive"))
      (node (ref "U1") (pin "7") (pinfunction "A1_7_7") (pintype "passive"))
      (node (ref "VR1") (pin "1") (pinfunction "1_1") (pintype "passive"))
    )
    (net (code "57") (name "TUBE_R") (class "Default")
      (node (ref "U$3") (pin "C") (pinfunction "G_C") (pintype "passive"))
      (node (ref "U1") (pin "10") (pinfunction "A2_10_10") (pintype "passive"))
      (node (ref "VR2") (pin "2") (pinfunction "2_2") (pintype "passive"))
    )
    (net (code "58") (name "unconnected-(CON1-Pad4)") (class "Default")
      (node (ref "CON1") (pin "4") (pinfunction "4_4") (pintype "input"))
    )
    (net (code "59") (name "unconnected-(IC3-CK-Pad2)") (class "Default")
      (node (ref "IC3") (pin "2") (pinfunction "CK_2") (pintype "output"))
    )
    (net (code "60") (name "unconnected-(IC3-DOUT-Pad5)") (class "Default")
      (node (ref "IC3") (pin "5") (pinfunction "DOUT_5") (pintype "output"))
    )
    (net (code "61") (name "unconnected-(IC3-HID0{slash}MS-Pad22)") (class "Default")
      (node (ref "IC3") (pin "22") (pinfunction "HID0/MS_22") (pintype "input"))
    )
    (net (code "62") (name "unconnected-(IC3-HID1{slash}MC-Pad23)") (class "Default")
      (node (ref "IC3") (pin "23") (pinfunction "HID1/MC_23") (pintype "input"))
    )
    (net (code "63") (name "unconnected-(IC3-HID2{slash}MD-Pad24)") (class "Default")
      (node (ref "IC3") (pin "24") (pinfunction "HID2/MD_24") (pintype "input"))
    )
    (net (code "64") (name "unconnected-(IC3-~{SSPND}-Pad27)") (class "Default")
      (node (ref "IC3") (pin "27") (pinfunction "~{SSPND}_27") (pintype "output"))
    )
  )
)
